# 3_3V.net
KiCad netlist of a schematic drawn in Altium Designer
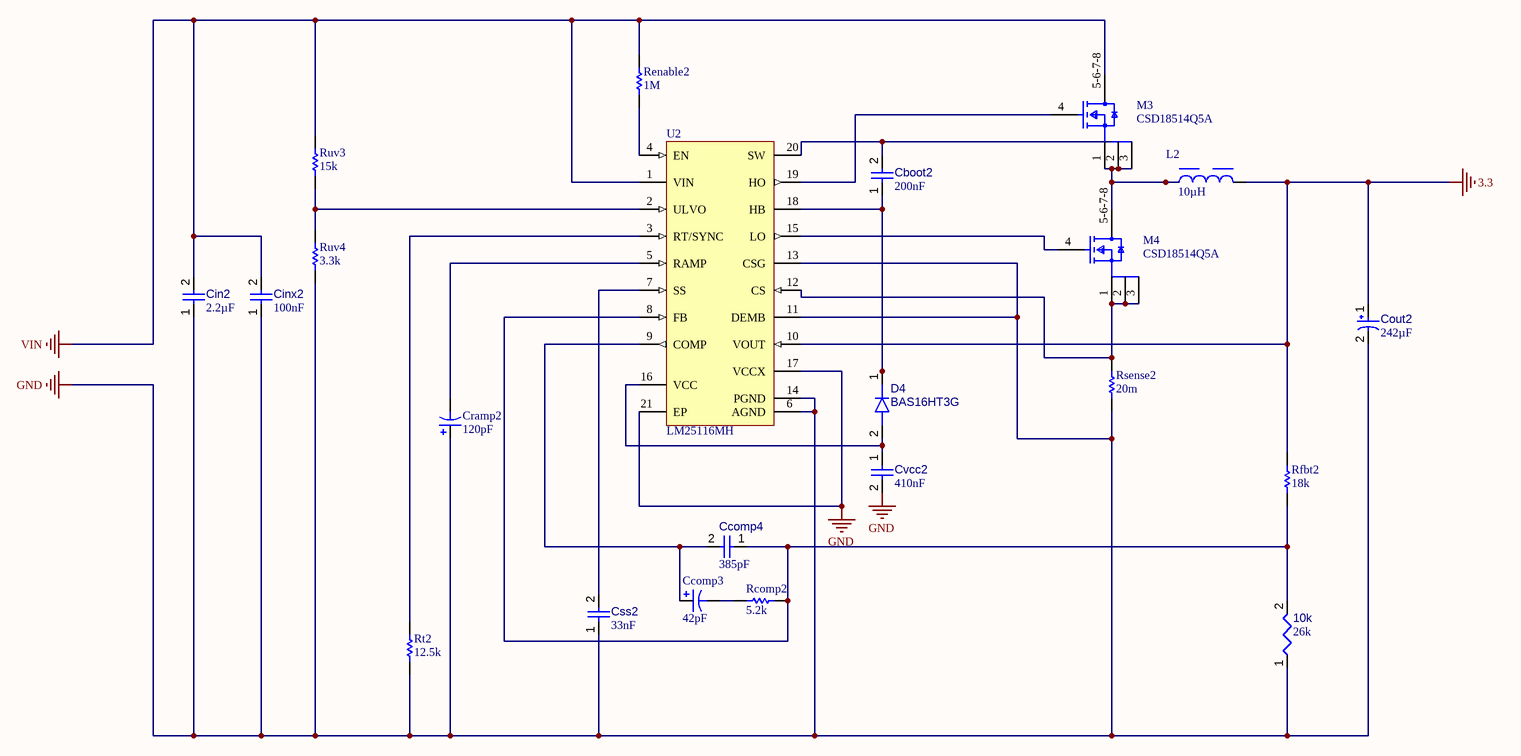
[diagram p0: 3.3V.SchDoc]

(export (version "E")
  (design (tool "Eeschema 10.0.6"))
  (components
    (comp (ref "10k")
      (value "26k")
      (footprint "RESC2013X50X35ML15T15")
      (description "Chip Resistor, 10 KOhm, +/- 1%, 125 mW, -55 to 155 degC, 0805 (2012 Metric)")
      (fields (field (name "TOLERANCE") "1%") (field (name "POWER") "125mW"))
      (libsource (lib "") (part "RES-2_1"))
    )
    (comp (ref "Cboot2")
      (value "200nF")
      (footprint "CAPC2013X95X50LL10T25")
      (description "Chip Capacitor, 100 nF, +/- 10%, 50 V, 0805 (2012 Metric)")
      (fields (field (name "TOLERANCE") "10%") (field (name "Comment") "Capacitor 100 nF +/-10% 50 V 0805"))
      (libsource (lib "Linköpings Universitet") (part "CAP-NP-2"))
    )
    (comp (ref "Ccomp3")
      (value "42pF")
      (footprint "C0805")
      (description "Polarized Capacitor (Surface Mount)")
      (fields (field (name "Comment") "Cap Pol3") (field (name "PUBLISHER") "Altium Limited"))
      (libsource (lib "Linköpings Universitet") (part "Cap Pol3"))
    )
    (comp (ref "Ccomp4")
      (value "385pF")
      (footprint "CAPC2013X135X45NL10T25")
      (description "Chip Capacitor, 10 uF, +/- 10%, 16 V, 0805 (2012 Metric)")
      (fields (field (name "TOLERANCE") "10%") (field (name "Comment") "Capacitor 10 uF +/- 10% 16 V 0805"))
      (libsource (lib "Linköpings Universitet") (part "CAP-NP-2"))
    )
    (comp (ref "Cin2")
      (value "2.2µF")
      (footprint "CAPC2013X135X45NL10T25")
      (description "Chip Capacitor, 1 uF, +/- 10%, 50 V, 0805 (2012 Metric)")
      (fields (field (name "TOLERANCE") "10%") (field (name "Comment") "Capacitor 1 uF +/- 10% 50 V 0805"))
      (libsource (lib "Linköpings Universitet") (part "CAP-NP-2"))
    )
    (comp (ref "Cinx2")
      (value "100nF")
      (footprint "CAPC2013X95X50LL10T25")
      (description "Chip Capacitor, 100 nF, +/- 10%, 50 V, 0805 (2012 Metric)")
      (fields (field (name "TOLERANCE") "10%") (field (name "Comment") "Capacitor 100 nF +/-10% 50 V 0805"))
      (libsource (lib "Linköpings Universitet") (part "CAP-NP-2"))
    )
    (comp (ref "Cout2")
      (value "242µF")
      (footprint "CAPPR65-500-1250X1000X1350")
      (description "Aluminum Electrolytic Capacitor, 220 uF, +/- 20%, 50 V, -40 to 85 degC, 2-Pin THD, RoHS, Bulk")
      (fields (field (name "MANUFACTURER") "Panasonic") (field (name "TOLERANCE") "20%"))
      (libsource (lib "Linköpings Universitet") (part "CAP-P-2"))
    )
    (comp (ref "Cramp2")
      (value "120pF")
      (footprint "C0805")
      (description "Polarized Capacitor (Surface Mount)")
      (fields (field (name "Comment") "Cap Pol3") (field (name "PUBLISHER") "Altium Limited"))
      (libsource (lib "Linköpings Universitet") (part "Cap Pol3"))
    )
    (comp (ref "Css2")
      (value "33nF")
      (footprint "CAPC2013X95X50LL10T25")
      (description "Chip Capacitor, 100 nF, +/- 10%, 50 V, 0805 (2012 Metric)")
      (fields (field (name "TOLERANCE") "10%") (field (name "Comment") "Capacitor 100 nF +/-10% 50 V 0805"))
      (libsource (lib "Linköpings Universitet") (part "CAP-NP-2"))
    )
    (comp (ref "Cvcc2")
      (value "410nF")
      (footprint "CAPC2013X145X50ML20T25")
      (description "Chip Capacitor, 1 uF, +/-10%, 25 V, 0805 (2012 Metric)")
      (fields (field (name "TOLERANCE") "10%") (field (name "Comment") "Capacitor 1 uF +/- 10% 25 V 0805"))
      (libsource (lib "Linköpings Universitet") (part "CAP-NP-2"))
    )
    (comp (ref "D4")
      (value "BAS16HT3G")
      (description "Rectifier Diode Small Signal Switching 0.2A 6ns Automotive 2-Pin SOD-323 T/R")
      (libsource (lib "Linköpings Universitet") (part "DIODE-2"))
    )
    (comp (ref "L2")
      (value "74438333022")
      (footprint "WE-MAPI_3010")
      (description "WE-MAPI SMT Power Inductor, size 3010, 2.2µH, 2.35A, 50MHz")
      (fields (field (name "MANUFACTURER") "Wurth Elektronik") (field (name "INDUCTANCE") "10µH"))
      (libsource (lib "Linköpings Universitet") (part "744383360068HT"))
    )
    (comp (ref "M3")
      (value "CSD18514Q5A")
      (footprint "FP-DQJ0008A-MFG")
      (description "40-V, N channel NexFET™ power MOSFET, single SON 5 mm x 6 mm, 4.9 mOhm 8-VSONP -55 to 150")
      (libsource (lib "Linköpings Universitet") (part "e0baf4780622716b99a4fe4ad34e686"))
    )
    (comp (ref "M4")
      (value "CSD18514Q5A")
      (footprint "FP-DQJ0008A-MFG")
      (description "40-V, N channel NexFET™ power MOSFET, single SON 5 mm x 6 mm, 4.9 mOhm 8-VSONP -55 to 150")
      (libsource (lib "Linköpings Universitet") (part "e0baf4780622716b99a4fe4ad34e686"))
    )
    (comp (ref "Rcomp2")
      (value "5.2k")
      (footprint "RESC2013X50X35ML15T15")
      (description "Chip Resistor, 0 Ohm, +/- 1%, 125 mW, -55 to 155 degC, 0805 (2012 Metric)")
      (fields (field (name "TOLERANCE") "1%") (field (name "POWER") "125mW"))
      (libsource (lib "Linköpings Universitet") (part "RES-2"))
    )
    (comp (ref "Renable2")
      (value "1M")
      (footprint "RESC2013X50X35ML15T15")
      (description "Chip Resistor, 0 Ohm, +/- 1%, 125 mW, -55 to 155 degC, 0805 (2012 Metric)")
      (fields (field (name "TOLERANCE") "1%") (field (name "POWER") "125mW"))
      (libsource (lib "Linköpings Universitet") (part "RES-2"))
    )
    (comp (ref "Rfbt2")
      (value "18k")
      (footprint "RESC2013X50X35ML15T15")
      (description "Chip Resistor, 0 Ohm, +/- 1%, 125 mW, -55 to 155 degC, 0805 (2012 Metric)")
      (fields (field (name "TOLERANCE") "1%") (field (name "POWER") "125mW"))
      (libsource (lib "Linköpings Universitet") (part "RES-2"))
    )
    (comp (ref "Rsense2")
      (value "20m")
      (footprint "RESC2013X50X35ML15T15")
      (description "Chip Resistor, 0 Ohm, +/- 1%, 125 mW, -55 to 155 degC, 0805 (2012 Metric)")
      (fields (field (name "TOLERANCE") "1%") (field (name "POWER") "125mW"))
      (libsource (lib "Linköpings Universitet") (part "RES-2"))
    )
    (comp (ref "Rt2")
      (value "12.5k")
      (footprint "RESC2013X50X35ML15T15")
      (description "Chip Resistor, 0 Ohm, +/- 1%, 125 mW, -55 to 155 degC, 0805 (2012 Metric)")
      (fields (field (name "TOLERANCE") "1%") (field (name "POWER") "125mW"))
      (libsource (lib "Linköpings Universitet") (part "RES-2"))
    )
    (comp (ref "Ruv3")
      (value "15k")
      (footprint "RESC2013X50X35ML15T15")
      (description "Chip Resistor, 0 Ohm, +/- 1%, 125 mW, -55 to 155 degC, 0805 (2012 Metric)")
      (fields (field (name "TOLERANCE") "1%") (field (name "POWER") "125mW"))
      (libsource (lib "Linköpings Universitet") (part "RES-2"))
    )
    (comp (ref "Ruv4")
      (value "3.3k")
      (footprint "RESC2013X50X35ML15T15")
      (description "Chip Resistor, 0 Ohm, +/- 1%, 125 mW, -55 to 155 degC, 0805 (2012 Metric)")
      (fields (field (name "TOLERANCE") "1%") (field (name "POWER") "125mW"))
      (libsource (lib "Linköpings Universitet") (part "RES-2"))
    )
    (comp (ref "U2")
      (value "LM25116MH")
      (footprint "PWP0020A_N")
      (description "6-42V Wide Vin, Current Mode Synchronous Buck Controller 20-HTSSOP -40 to 125")
      (libsource (lib "Linköpings Universitet") (part "PM-REG-LM25116MH-21"))
    )
  )
  (nets
    (net (code "1") (name "3.3") (class "Default")
      (node (ref "Cout2") (pin "1") (pinfunction "1_1") (pintype "passive"))
      (node (ref "L2") (pin "2") (pinfunction "2_2") (pintype "passive"))
      (node (ref "Rfbt2") (pin "2") (pinfunction "2_2") (pintype "passive"))
      (node (ref "U2") (pin "10") (pinfunction "VOUT_10") (pintype "input"))
    )
    (net (code "2") (name "GND") (class "Default")
      (node (ref "10k") (pin "1") (pinfunction "1_1") (pintype "passive"))
      (node (ref "Cin2") (pin "1") (pinfunction "1_1") (pintype "passive"))
      (node (ref "Cinx2") (pin "1") (pinfunction "1_1") (pintype "passive"))
      (node (ref "Cout2") (pin "2") (pinfunction "2_2") (pintype "passive"))
      (node (ref "Cramp2") (pin "1") (pinfunction "1_1") (pintype "passive"))
      (node (ref "Css2") (pin "1") (pinfunction "1_1") (pintype "passive"))
      (node (ref "Cvcc2") (pin "2") (pinfunction "2_2") (pintype "passive"))
      (node (ref "Rsense2") (pin "1") (pinfunction "1_1") (pintype "passive"))
      (node (ref "Rt2") (pin "1") (pinfunction "1_1") (pintype "passive"))
      (node (ref "Ruv4") (pin "1") (pinfunction "1_1") (pintype "passive"))
      (node (ref "U2") (pin "11") (pinfunction "DEMB_11") (pintype "passive"))
      (node (ref "U2") (pin "13") (pinfunction "CSG_13") (pintype "passive"))
      (node (ref "U2") (pin "14") (pinfunction "PGND_14") (pintype "power_in"))
      (node (ref "U2") (pin "17") (pinfunction "VCCX_17") (pintype "power_in"))
      (node (ref "U2") (pin "21") (pinfunction "EP_21") (pintype "power_in"))
      (node (ref "U2") (pin "6") (pinfunction "AGND_6") (pintype "power_in"))
    )
    (net (code "3") (name "Net-(Ccomp3-Pad2)") (class "Default")
      (node (ref "Ccomp3") (pin "2") (pinfunction "2_2") (pintype "passive"))
      (node (ref "Rcomp2") (pin "2") (pinfunction "2_2") (pintype "passive"))
    )
    (net (code "4") (name "Net-(D4-A)") (class "Default")
      (node (ref "Cvcc2") (pin "1") (pinfunction "1_1") (pintype "passive"))
      (node (ref "D4") (pin "2") (pinfunction "A_2") (pintype "passive"))
      (node (ref "U2") (pin "16") (pinfunction "VCC_16") (pintype "power_in"))
    )
    (net (code "5") (name "Net-(D4-K)") (class "Default")
      (node (ref "Cboot2") (pin "1") (pinfunction "1_1") (pintype "passive"))
      (node (ref "D4") (pin "1") (pinfunction "K_1") (pintype "passive"))
      (node (ref "U2") (pin "18") (pinfunction "HB_18") (pintype "passive"))
    )
    (net (code "6") (name "Net-(M3-G)") (class "Default")
      (node (ref "M3") (pin "4") (pinfunction "G_4") (pintype "passive"))
      (node (ref "U2") (pin "19") (pinfunction "HO_19") (pintype "output"))
    )
    (net (code "7") (name "Net-(M4-D)") (class "Default")
      (node (ref "L2") (pin "1") (pinfunction "1_1") (pintype "passive"))
      (node (ref "M3") (pin "1") (pinfunction "S_1") (pintype "passive"))
      (node (ref "M3") (pin "2") (pinfunction "S_2") (pintype "passive"))
      (node (ref "M3") (pin "3") (pinfunction "S_3") (pintype "passive"))
      (node (ref "M4") (pin "5-6-7-8") (pinfunction "D_5-6-7-8") (pintype "passive"))
    )
    (net (code "8") (name "Net-(M4-G)") (class "Default")
      (node (ref "M4") (pin "4") (pinfunction "G_4") (pintype "passive"))
      (node (ref "U2") (pin "15") (pinfunction "LO_15") (pintype "output"))
    )
    (net (code "9") (name "Net-(U2-COMP)") (class "Default")
      (node (ref "Ccomp3") (pin "1") (pinfunction "1_1") (pintype "passive"))
      (node (ref "Ccomp4") (pin "2") (pinfunction "2_2") (pintype "passive"))
      (node (ref "U2") (pin "9") (pinfunction "COMP_9") (pintype "output"))
    )
    (net (code "10") (name "Net-(U2-CS)") (class "Default")
      (node (ref "M4") (pin "1") (pinfunction "S_1") (pintype "passive"))
      (node (ref "M4") (pin "2") (pinfunction "S_2") (pintype "passive"))
      (node (ref "M4") (pin "3") (pinfunction "S_3") (pintype "passive"))
      (node (ref "Rsense2") (pin "2") (pinfunction "2_2") (pintype "passive"))
      (node (ref "U2") (pin "12") (pinfunction "CS_12") (pintype "input"))
    )
    (net (code "11") (name "Net-(U2-EN)") (class "Default")
      (node (ref "Renable2") (pin "1") (pinfunction "1_1") (pintype "passive"))
      (node (ref "U2") (pin "4") (pinfunction "EN_4") (pintype "input"))
    )
    (net (code "12") (name "Net-(U2-FB)") (class "Default")
      (node (ref "10k") (pin "2") (pinfunction "2_2") (pintype "passive"))
      (node (ref "Ccomp4") (pin "1") (pinfunction "1_1") (pintype "passive"))
      (node (ref "Rcomp2") (pin "1") (pinfunction "1_1") (pintype "passive"))
      (node (ref "Rfbt2") (pin "1") (pinfunction "1_1") (pintype "passive"))
      (node (ref "U2") (pin "8") (pinfunction "FB_8") (pintype "input"))
    )
    (net (code "13") (name "Net-(U2-RAMP)") (class "Default")
      (node (ref "Cramp2") (pin "2") (pinfunction "2_2") (pintype "passive"))
      (node (ref "U2") (pin "5") (pinfunction "RAMP_5") (pintype "input"))
    )
    (net (code "14") (name "Net-(U2-RT{slash}SYNC)") (class "Default")
      (node (ref "Rt2") (pin "2") (pinfunction "2_2") (pintype "passive"))
      (node (ref "U2") (pin "3") (pinfunction "RT/SYNC_3") (pintype "input"))
    )
    (net (code "15") (name "Net-(U2-SS)") (class "Default")
      (node (ref "Css2") (pin "2") (pinfunction "2_2") (pintype "passive"))
      (node (ref "U2") (pin "7") (pinfunction "SS_7") (pintype "input"))
    )
    (net (code "16") (name "Net-(U2-SW)") (class "Default")
      (node (ref "Cboot2") (pin "2") (pinfunction "2_2") (pintype "passive"))
      (node (ref "U2") (pin "20") (pinfunction "SW_20") (pintype "power_in"))
    )
    (net (code "17") (name "Net-(U2-ULVO)") (class "Default")
      (node (ref "Ruv3") (pin "1") (pinfunction "1_1") (pintype "passive"))
      (node (ref "Ruv4") (pin "2") (pinfunction "2_2") (pintype "passive"))
      (node (ref "U2") (pin "2") (pinfunction "ULVO_2") (pintype "input"))
    )
    (net (code "18") (name "VIN") (class "Default")
      (node (ref "Cin2") (pin "2") (pinfunction "2_2") (pintype "passive"))
      (node (ref "Cinx2") (pin "2") (pinfunction "2_2") (pintype "passive"))
      (node (ref "M3") (pin "5-6-7-8") (pinfunction "D_5-6-7-8") (pintype "passive"))
      (node (ref "Renable2") (pin "2") (pinfunction "2_2") (pintype "passive"))
      (node (ref "Ruv3") (pin "2") (pinfunction "2_2") (pintype "passive"))
      (node (ref "U2") (pin "1") (pinfunction "VIN_1") (pintype "power_in"))
    )
  )
)
